# powerblade_1v0.net
KiCad netlist of a schematic drawn in EAGLE
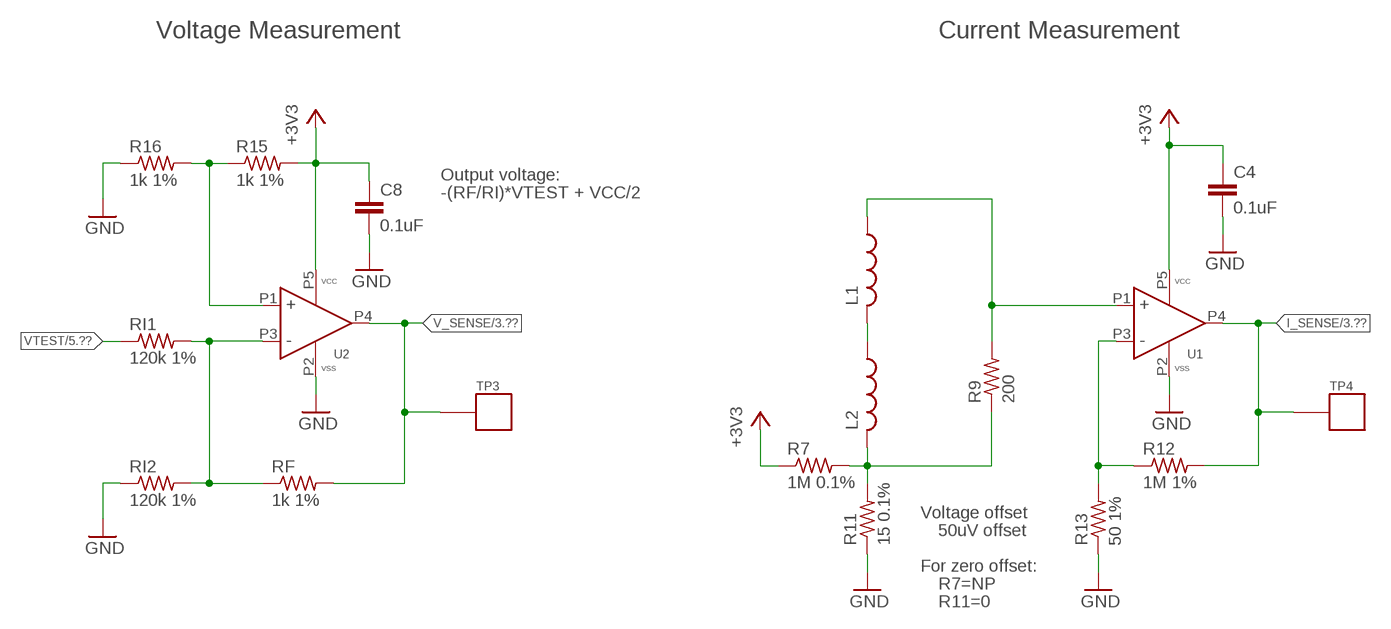
[diagram p0: schematic, sheet 1]
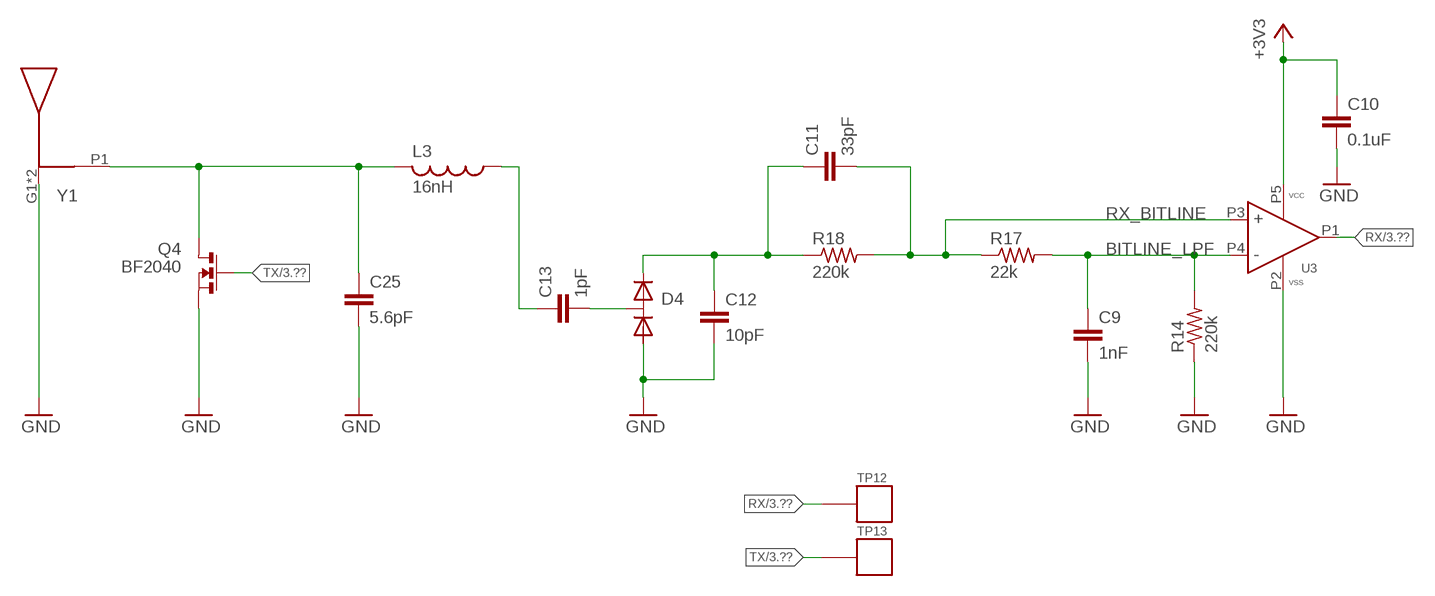
[diagram p1: schematic, sheet 2]
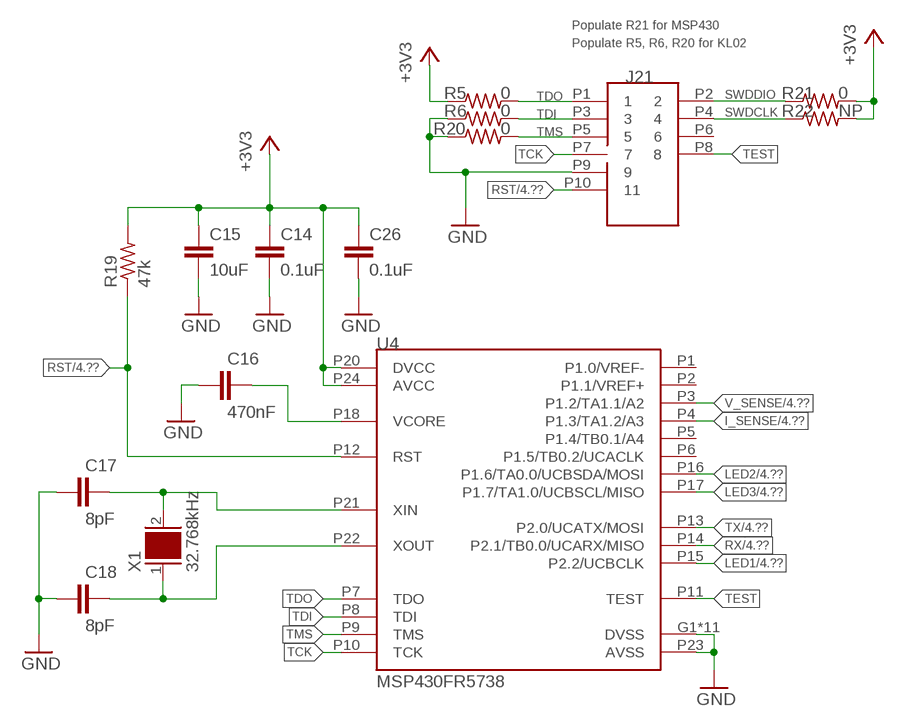
[diagram p2: schematic, sheet 3]
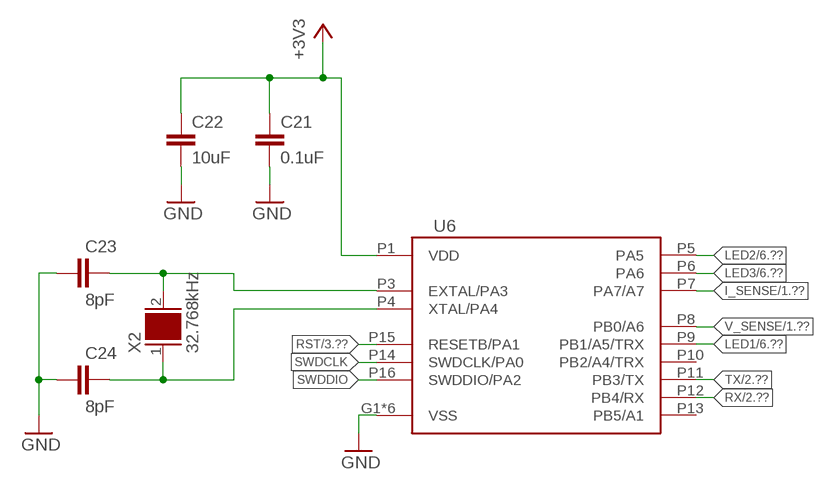
[diagram p3: schematic, sheet 4]
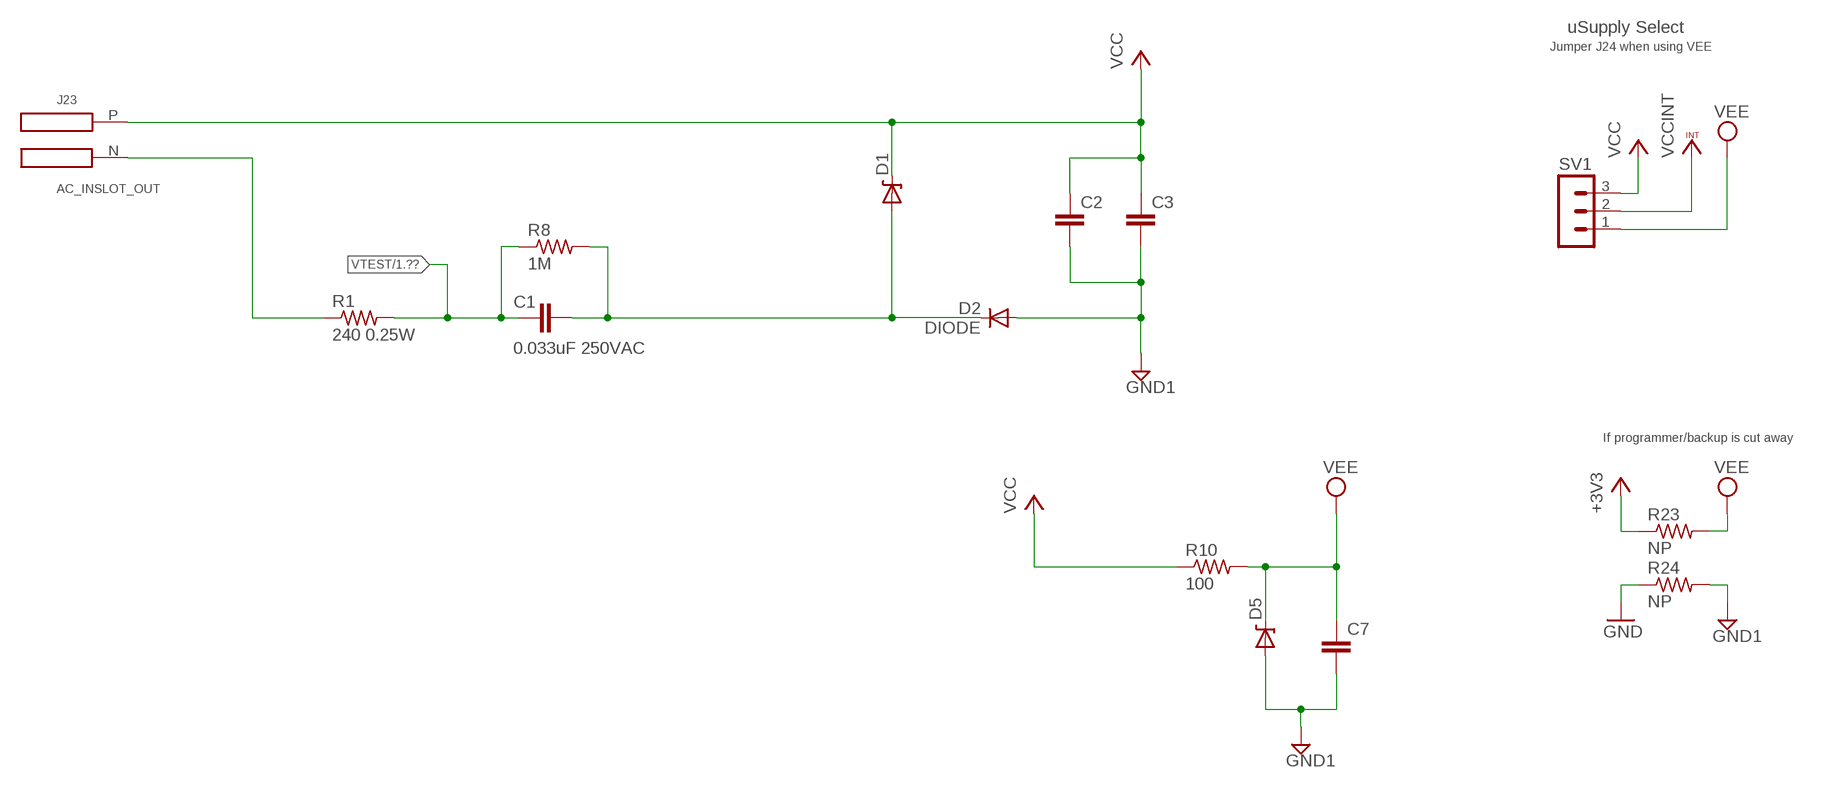
[diagram p4: schematic, sheet 5]
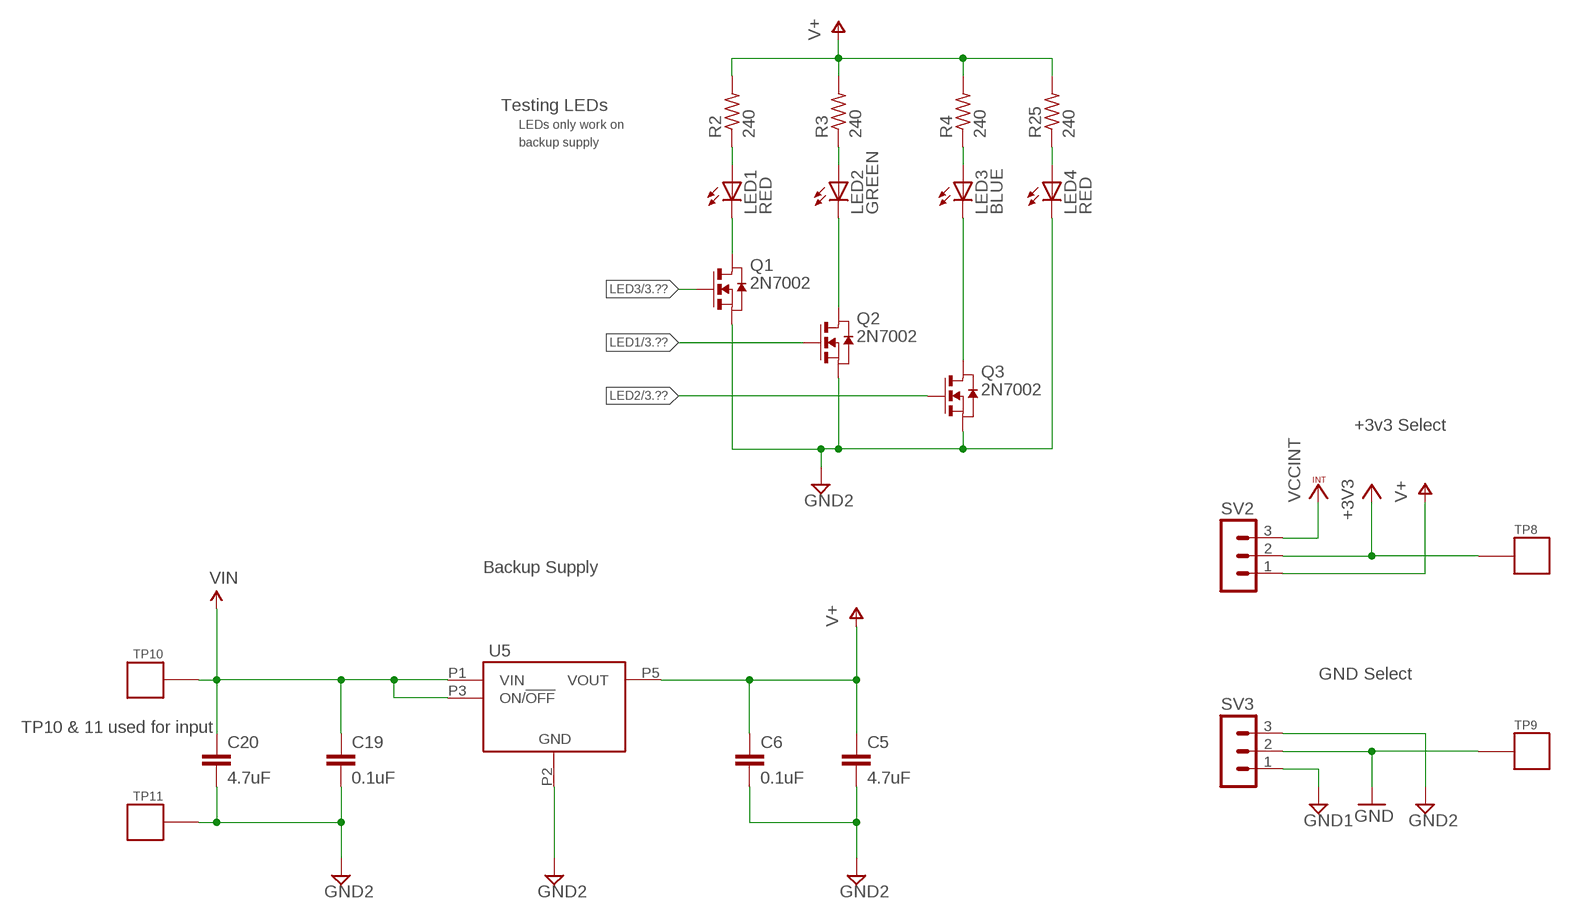
[diagram p5: schematic, sheet 6]

(export (version "E")
  (design (tool "Eeschema 10.0.6"))
  (components
    (comp (ref "C1")
      (value "0.033uF 250VAC")
      (footprint "eagle-import:C2220K")
      (libsource (lib "eagle-import") (part "C-EUC2220K"))
    )
    (comp (ref "C2")
      (value "C-EUC0805")
      (footprint "eagle-import:C0805")
      (libsource (lib "eagle-import") (part "C-EUC0805"))
    )
    (comp (ref "C3")
      (value "C-EUC0603")
      (footprint "eagle-import:C0603")
      (libsource (lib "eagle-import") (part "C-EUC0603"))
    )
    (comp (ref "C7")
      (value "C-EUC0603")
      (footprint "eagle-import:C0603")
      (libsource (lib "eagle-import") (part "C-EUC0603"))
    )
    (comp (ref "D1")
      (value "ZENERBZT52")
      (footprint "eagle-import:BZT52")
      (libsource (lib "eagle-import") (part "ZENERBZT52"))
    )
    (comp (ref "D2")
      (value "DIODE")
      (footprint "eagle-import:BAS521")
      (libsource (lib "eagle-import") (part "DIODE"))
    )
    (comp (ref "D5")
      (value "ZENERBZT52")
      (footprint "eagle-import:BZT52")
      (libsource (lib "eagle-import") (part "ZENERBZT52"))
    )
    (comp (ref "J23")
      (value "AC_INSLOT_OUT")
      (footprint "eagle-import:AC_SLOT_OUT")
      (libsource (lib "eagle-import") (part "AC_INSLOT_OUT"))
    )
    (comp (ref "R1")
      (value "240 0.25W")
      (footprint "eagle-import:R0603")
      (libsource (lib "eagle-import") (part "R-US_R0603"))
    )
    (comp (ref "R8")
      (value "1M")
      (footprint "eagle-import:R0603")
      (libsource (lib "eagle-import") (part "R-US_R0603"))
    )
    (comp (ref "R10")
      (value "100")
      (footprint "eagle-import:R0603")
      (libsource (lib "eagle-import") (part "R-US_R0603"))
    )
    (comp (ref "R23")
      (value "NP")
      (footprint "eagle-import:R0603")
      (libsource (lib "eagle-import") (part "R-US_R0603"))
    )
    (comp (ref "R24")
      (value "NP")
      (footprint "eagle-import:R0603")
      (libsource (lib "eagle-import") (part "R-US_R0603"))
    )
    (comp (ref "SV1")
      (value "MA03-1STR")
      (footprint "eagle-import:MA03-1")
      (libsource (lib "eagle-import") (part "MA03-1STR"))
    )
    (comp (ref "C5")
      (value "4.7uF")
      (footprint "eagle-import:C0603")
      (libsource (lib "eagle-import") (part "C-EUC0603"))
    )
    (comp (ref "C6")
      (value "0.1uF")
      (footprint "eagle-import:C0603")
      (libsource (lib "eagle-import") (part "C-EUC0603"))
    )
    (comp (ref "C19")
      (value "0.1uF")
      (footprint "eagle-import:C0603")
      (libsource (lib "eagle-import") (part "C-EUC0603"))
    )
    (comp (ref "C20")
      (value "4.7uF")
      (footprint "eagle-import:C0603")
      (libsource (lib "eagle-import") (part "C-EUC0603"))
    )
    (comp (ref "LED1")
      (value "RED")
      (footprint "eagle-import:LED-0603")
      (libsource (lib "eagle-import") (part "LED0603"))
    )
    (comp (ref "LED2")
      (value "GREEN")
      (footprint "eagle-import:LED-0603")
      (libsource (lib "eagle-import") (part "LED0603"))
    )
    (comp (ref "LED3")
      (value "BLUE")
      (footprint "eagle-import:LED-0603")
      (libsource (lib "eagle-import") (part "LED0603"))
    )
    (comp (ref "LED4")
      (value "RED")
      (footprint "eagle-import:LED-0603")
      (libsource (lib "eagle-import") (part "LED0603"))
    )
    (comp (ref "Q1")
      (value "2N7002")
      (footprint "eagle-import:SC-70-3")
      (libsource (lib "eagle-import") (part "2N7002"))
    )
    (comp (ref "Q2")
      (value "2N7002")
      (footprint "eagle-import:SC-70-3")
      (libsource (lib "eagle-import") (part "2N7002"))
    )
    (comp (ref "Q3")
      (value "2N7002")
      (footprint "eagle-import:SC-70-3")
      (libsource (lib "eagle-import") (part "2N7002"))
    )
    (comp (ref "R2")
      (value "240")
      (footprint "eagle-import:R0603")
      (libsource (lib "eagle-import") (part "R-US_R0603"))
    )
    (comp (ref "R3")
      (value "240")
      (footprint "eagle-import:R0603")
      (libsource (lib "eagle-import") (part "R-US_R0603"))
    )
    (comp (ref "R4")
      (value "240")
      (footprint "eagle-import:R0603")
      (libsource (lib "eagle-import") (part "R-US_R0603"))
    )
    (comp (ref "R25")
      (value "240")
      (footprint "eagle-import:R0603")
      (libsource (lib "eagle-import") (part "R-US_R0603"))
    )
    (comp (ref "SV2")
      (value "MA03-1STR")
      (footprint "eagle-import:MA03-1")
      (libsource (lib "eagle-import") (part "MA03-1STR"))
    )
    (comp (ref "SV3")
      (value "MA03-1STR")
      (footprint "eagle-import:MA03-1")
      (libsource (lib "eagle-import") (part "MA03-1STR"))
    )
    (comp (ref "TP8")
      (value "TP_STD")
      (footprint "eagle-import:TP")
      (libsource (lib "eagle-import") (part "TP_STD"))
    )
    (comp (ref "TP9")
      (value "TP_STD")
      (footprint "eagle-import:TP")
      (libsource (lib "eagle-import") (part "TP_STD"))
    )
    (comp (ref "TP10")
      (value "TP_STD")
      (footprint "eagle-import:TP")
      (libsource (lib "eagle-import") (part "TP_STD"))
    )
    (comp (ref "TP11")
      (value "TP_STD")
      (footprint "eagle-import:TP")
      (libsource (lib "eagle-import") (part "TP_STD"))
    )
    (comp (ref "U5")
      (value "LP2980")
      (footprint "eagle-import:SOT-23-5")
      (libsource (lib "eagle-import") (part "LP2980"))
    )
    (comp (ref "C14")
      (value "0.1uF")
      (footprint "eagle-import:C0603")
      (libsource (lib "eagle-import") (part "C-EUC0603"))
    )
    (comp (ref "C15")
      (value "10uF")
      (footprint "eagle-import:C0603")
      (libsource (lib "eagle-import") (part "C-EUC0603"))
    )
    (comp (ref "C16")
      (value "470nF")
      (footprint "eagle-import:C0603")
      (libsource (lib "eagle-import") (part "C-EUC0603"))
    )
    (comp (ref "C17")
      (value "8pF")
      (footprint "eagle-import:C0603")
      (libsource (lib "eagle-import") (part "C-EUC0603"))
    )
    (comp (ref "C18")
      (value "8pF")
      (footprint "eagle-import:C0603")
      (libsource (lib "eagle-import") (part "C-EUC0603"))
    )
    (comp (ref "C26")
      (value "0.1uF")
      (footprint "eagle-import:C0603")
      (libsource (lib "eagle-import") (part "C-EUC0603"))
    )
    (comp (ref "J21")
      (value "JTAG_14PIN_IDC-NL")
      (footprint "eagle-import:TC2050-IDC-NL-430")
      (fields (field (name "TAG-CONNECT") "TC2050-IDC-NL-430"))
      (libsource (lib "eagle-import") (part "JTAG_14PIN_IDC-NL"))
    )
    (comp (ref "R5")
      (value "0")
      (footprint "eagle-import:R0603")
      (libsource (lib "eagle-import") (part "R-US_R0603"))
    )
    (comp (ref "R6")
      (value "0")
      (footprint "eagle-import:R0603")
      (libsource (lib "eagle-import") (part "R-US_R0603"))
    )
    (comp (ref "R19")
      (value "47k")
      (footprint "eagle-import:R0603")
      (libsource (lib "eagle-import") (part "R-US_R0603"))
    )
    (comp (ref "R20")
      (value "0")
      (footprint "eagle-import:R0603")
      (libsource (lib "eagle-import") (part "R-US_R0603"))
    )
    (comp (ref "R21")
      (value "0")
      (footprint "eagle-import:R0603")
      (libsource (lib "eagle-import") (part "R-US_R0603"))
    )
    (comp (ref "R22")
      (value "NP")
      (footprint "eagle-import:R0603")
      (libsource (lib "eagle-import") (part "R-US_R0603"))
    )
    (comp (ref "U4")
      (value "MSP430FR5738")
      (footprint "eagle-import:VQFN-24")
      (libsource (lib "eagle-import") (part "MSP430FR5738"))
    )
    (comp (ref "X1")
      (value "32.768kHz")
      (footprint "eagle-import:0805")
      (libsource (lib "eagle-import") (part "CRYSTAL_0805"))
    )
    (comp (ref "C9")
      (value "1nF")
      (footprint "eagle-import:C0603")
      (libsource (lib "eagle-import") (part "C-EUC0603"))
    )
    (comp (ref "C10")
      (value "0.1uF")
      (footprint "eagle-import:C0603")
      (libsource (lib "eagle-import") (part "C-EUC0603"))
    )
    (comp (ref "C11")
      (value "33pF")
      (footprint "eagle-import:C0603")
      (libsource (lib "eagle-import") (part "C-EUC0603"))
    )
    (comp (ref "C12")
      (value "10pF")
      (footprint "eagle-import:C0603")
      (libsource (lib "eagle-import") (part "C-EUC0603"))
    )
    (comp (ref "C13")
      (value "1pF")
      (footprint "eagle-import:C0603")
      (libsource (lib "eagle-import") (part "C-EUC0603"))
    )
    (comp (ref "C25")
      (value "5.6pF")
      (footprint "eagle-import:C0603")
      (libsource (lib "eagle-import") (part "C-EUC0603"))
    )
    (comp (ref "D4")
      (value "HSMS-285C")
      (footprint "eagle-import:SOT-323")
      (libsource (lib "eagle-import") (part "HSMS-285C"))
    )
    (comp (ref "L3")
      (value "16nH")
      (footprint "eagle-import:L0603")
      (libsource (lib "eagle-import") (part "L-USL0603"))
    )
    (comp (ref "Q4")
      (value "BF2040")
      (footprint "eagle-import:SOT-143")
      (libsource (lib "eagle-import") (part "BF2040"))
    )
    (comp (ref "R14")
      (value "220k")
      (footprint "eagle-import:R0603")
      (libsource (lib "eagle-import") (part "R-US_R0603"))
    )
    (comp (ref "R17")
      (value "22k")
      (footprint "eagle-import:R0603")
      (libsource (lib "eagle-import") (part "R-US_R0603"))
    )
    (comp (ref "R18")
      (value "220k")
      (footprint "eagle-import:R0603")
      (libsource (lib "eagle-import") (part "R-US_R0603"))
    )
    (comp (ref "TP12")
      (value "TP_STD")
      (footprint "eagle-import:TP")
      (libsource (lib "eagle-import") (part "TP_STD"))
    )
    (comp (ref "TP13")
      (value "TP_STD")
      (footprint "eagle-import:TP")
      (libsource (lib "eagle-import") (part "TP_STD"))
    )
    (comp (ref "U3")
      (value "NCS2200S")
      (footprint "eagle-import:SC70-5")
      (libsource (lib "eagle-import") (part "NCS2200S"))
    )
    (comp (ref "Y1")
      (value "ANT-USP")
      (footprint "eagle-import:ANT-USP")
      (fields (field (name "DIGIKEY") "ANT-916-USP-ND"))
      (libsource (lib "eagle-import") (part "ANT-USP"))
    )
    (comp (ref "C21")
      (value "0.1uF")
      (footprint "eagle-import:C0603")
      (libsource (lib "eagle-import") (part "C-EUC0603"))
    )
    (comp (ref "C22")
      (value "10uF")
      (footprint "eagle-import:C0603")
      (libsource (lib "eagle-import") (part "C-EUC0603"))
    )
    (comp (ref "C23")
      (value "8pF")
      (footprint "eagle-import:C0603")
      (libsource (lib "eagle-import") (part "C-EUC0603"))
    )
    (comp (ref "C24")
      (value "8pF")
      (footprint "eagle-import:C0603")
      (libsource (lib "eagle-import") (part "C-EUC0603"))
    )
    (comp (ref "U6")
      (value "KL02")
      (footprint "eagle-import:WQFN-16")
      (libsource (lib "eagle-import") (part "KL02"))
    )
    (comp (ref "X2")
      (value "32.768kHz")
      (footprint "eagle-import:0805")
      (libsource (lib "eagle-import") (part "CRYSTAL_0805"))
    )
    (comp (ref "C4")
      (value "0.1uF")
      (footprint "eagle-import:C0402")
      (libsource (lib "eagle-import") (part "C-EUC0402"))
    )
    (comp (ref "C8")
      (value "0.1uF")
      (footprint "eagle-import:C0402")
      (libsource (lib "eagle-import") (part "C-EUC0402"))
    )
    (comp (ref "L1")
      (value "L-USL0805")
      (footprint "eagle-import:L0805")
      (libsource (lib "eagle-import") (part "L-USL0805"))
    )
    (comp (ref "L2")
      (value "L-USL0805")
      (footprint "eagle-import:L0805")
      (libsource (lib "eagle-import") (part "L-USL0805"))
    )
    (comp (ref "R7")
      (value "1M 0.1%")
      (footprint "eagle-import:R0603")
      (libsource (lib "eagle-import") (part "R-US_R0603"))
    )
    (comp (ref "R9")
      (value "200")
      (footprint "eagle-import:R0603")
      (libsource (lib "eagle-import") (part "R-US_R0603"))
    )
    (comp (ref "R11")
      (value "15 0.1%")
      (footprint "eagle-import:R0603")
      (libsource (lib "eagle-import") (part "R-US_R0603"))
    )
    (comp (ref "R12")
      (value "1M 1%")
      (footprint "eagle-import:R0603")
      (libsource (lib "eagle-import") (part "R-US_R0603"))
    )
    (comp (ref "R13")
      (value "50 1%")
      (footprint "eagle-import:R0603")
      (libsource (lib "eagle-import") (part "R-US_R0603"))
    )
    (comp (ref "R15")
      (value "1k 1%")
      (footprint "eagle-import:R0603")
      (libsource (lib "eagle-import") (part "R-US_R0603"))
    )
    (comp (ref "R16")
      (value "1k 1%")
      (footprint "eagle-import:R0603")
      (libsource (lib "eagle-import") (part "R-US_R0603"))
    )
    (comp (ref "RF")
      (value "1k 1%")
      (footprint "eagle-import:R0603")
      (libsource (lib "eagle-import") (part "R-US_R0603"))
    )
    (comp (ref "RI1")
      (value "120k 1%")
      (footprint "eagle-import:R0603")
      (libsource (lib "eagle-import") (part "R-US_R0603"))
    )
    (comp (ref "RI2")
      (value "120k 1%")
      (footprint "eagle-import:R0603")
      (libsource (lib "eagle-import") (part "R-US_R0603"))
    )
    (comp (ref "TP3")
      (value "TP_STD")
      (footprint "eagle-import:TP")
      (libsource (lib "eagle-import") (part "TP_STD"))
    )
    (comp (ref "TP4")
      (value "TP_STD")
      (footprint "eagle-import:TP")
      (libsource (lib "eagle-import") (part "TP_STD"))
    )
    (comp (ref "U1")
      (value "MAX9910")
      (footprint "eagle-import:SC70-5")
      (libsource (lib "eagle-import") (part "MAX9910"))
    )
    (comp (ref "U2")
      (value "MAX9910")
      (footprint "eagle-import:SC70-5")
      (libsource (lib "eagle-import") (part "MAX9910"))
    )
  )
  (nets
    (net (code "1") (name "+3V3") (class "Default")
      (node (ref "C10") (pin "1") (pinfunction "1_1") (pintype "passive"))
      (node (ref "C14") (pin "1") (pinfunction "1_1") (pintype "passive"))
      (node (ref "C15") (pin "1") (pinfunction "1_1") (pintype "passive"))
      (node (ref "C21") (pin "1") (pinfunction "1_1") (pintype "passive"))
      (node (ref "C22") (pin "1") (pinfunction "1_1") (pintype "passive"))
      (node (ref "C26") (pin "1") (pinfunction "1_1") (pintype "passive"))
      (node (ref "C4") (pin "1") (pinfunction "1_1") (pintype "passive"))
      (node (ref "C8") (pin "1") (pinfunction "1_1") (pintype "passive"))
      (node (ref "R15") (pin "2") (pinfunction "2_2") (pintype "passive"))
      (node (ref "R19") (pin "2") (pinfunction "2_2") (pintype "passive"))
      (node (ref "R21") (pin "2") (pinfunction "2_2") (pintype "passive"))
      (node (ref "R22") (pin "2") (pinfunction "2_2") (pintype "passive"))
      (node (ref "R23") (pin "1") (pinfunction "1_1") (pintype "passive"))
      (node (ref "R5") (pin "1") (pinfunction "1_1") (pintype "passive"))
      (node (ref "R7") (pin "1") (pinfunction "1_1") (pintype "passive"))
      (node (ref "SV2") (pin "2") (pinfunction "2_2") (pintype "passive"))
      (node (ref "TP8") (pin "P$1") (pinfunction "P$1_P$1") (pintype "bidirectional"))
      (node (ref "U1") (pin "P5") (pinfunction "VCC_P5") (pintype "bidirectional"))
      (node (ref "U2") (pin "P5") (pinfunction "VCC_P5") (pintype "bidirectional"))
      (node (ref "U3") (pin "P5") (pinfunction "VCC_P5") (pintype "bidirectional"))
      (node (ref "U4") (pin "P20") (pinfunction "DVCC_P20") (pintype "bidirectional"))
      (node (ref "U4") (pin "P24") (pinfunction "AVCC_P24") (pintype "bidirectional"))
      (node (ref "U6") (pin "P1") (pinfunction "VDD_P1") (pintype "bidirectional"))
    )
    (net (code "2") (name "BITLINE_LPF") (class "Default")
      (node (ref "C9") (pin "1") (pinfunction "1_1") (pintype "passive"))
      (node (ref "R14") (pin "2") (pinfunction "2_2") (pintype "passive"))
      (node (ref "R17") (pin "2") (pinfunction "2_2") (pintype "passive"))
      (node (ref "U3") (pin "P4") (pinfunction "IN-_P4") (pintype "bidirectional"))
    )
    (net (code "3") (name "GND") (class "Default")
      (node (ref "C10") (pin "2") (pinfunction "2_2") (pintype "passive"))
      (node (ref "C12") (pin "2") (pinfunction "2_2") (pintype "passive"))
      (node (ref "C14") (pin "2") (pinfunction "2_2") (pintype "passive"))
      (node (ref "C15") (pin "2") (pinfunction "2_2") (pintype "passive"))
      (node (ref "C16") (pin "1") (pinfunction "1_1") (pintype "passive"))
      (node (ref "C17") (pin "1") (pinfunction "1_1") (pintype "passive"))
      (node (ref "C18") (pin "1") (pinfunction "1_1") (pintype "passive"))
      (node (ref "C21") (pin "2") (pinfunction "2_2") (pintype "passive"))
      (node (ref "C22") (pin "2") (pinfunction "2_2") (pintype "passive"))
      (node (ref "C23") (pin "1") (pinfunction "1_1") (pintype "passive"))
      (node (ref "C24") (pin "1") (pinfunction "1_1") (pintype "passive"))
      (node (ref "C25") (pin "2") (pinfunction "2_2") (pintype "passive"))
      (node (ref "C26") (pin "2") (pinfunction "2_2") (pintype "passive"))
      (node (ref "C4") (pin "2") (pinfunction "2_2") (pintype "passive"))
      (node (ref "C8") (pin "2") (pinfunction "2_2") (pintype "passive"))
      (node (ref "C9") (pin "2") (pinfunction "2_2") (pintype "passive"))
      (node (ref "D4") (pin "P1") (pinfunction "P1_P1") (pintype "passive"))
      (node (ref "J21") (pin "P9") (pinfunction "9_P9") (pintype "bidirectional"))
      (node (ref "Q4") (pin "P1") (pinfunction "S_P1") (pintype "passive"))
      (node (ref "R11") (pin "1") (pinfunction "1_1") (pintype "passive"))
      (node (ref "R13") (pin "1") (pinfunction "1_1") (pintype "passive"))
      (node (ref "R14") (pin "1") (pinfunction "1_1") (pintype "passive"))
      (node (ref "R16") (pin "1") (pinfunction "1_1") (pintype "passive"))
      (node (ref "R20") (pin "1") (pinfunction "1_1") (pintype "passive"))
      (node (ref "R24") (pin "1") (pinfunction "1_1") (pintype "passive"))
      (node (ref "R6") (pin "1") (pinfunction "1_1") (pintype "passive"))
      (node (ref "RI2") (pin "1") (pinfunction "1_1") (pintype "passive"))
      (node (ref "SV3") (pin "2") (pinfunction "2_2") (pintype "passive"))
      (node (ref "TP9") (pin "P$1") (pinfunction "P$1_P$1") (pintype "bidirectional"))
      (node (ref "U1") (pin "P2") (pinfunction "VSS_P2") (pintype "bidirectional"))
      (node (ref "U2") (pin "P2") (pinfunction "VSS_P2") (pintype "bidirectional"))
      (node (ref "U3") (pin "P2") (pinfunction "VSS_P2") (pintype "bidirectional"))
      (node (ref "U4") (pin "G1") (pinfunction "DVSS_G1") (pintype "bidirectional"))
      (node (ref "U4") (pin "G2") (pinfunction "DVSS_G2") (pintype "bidirectional"))
      (node (ref "U4") (pin "G3") (pinfunction "DVSS_G3") (pintype "bidirectional"))
      (node (ref "U4") (pin "G4") (pinfunction "DVSS_G4") (pintype "bidirectional"))
      (node (ref "U4") (pin "G5") (pinfunction "DVSS_G5") (pintype "bidirectional"))
      (node (ref "U4") (pin "G6") (pinfunction "DVSS_G6") (pintype "bidirectional"))
      (node (ref "U4") (pin "G7") (pinfunction "DVSS_G7") (pintype "bidirectional"))
      (node (ref "U4") (pin "G8") (pinfunction "DVSS_G8") (pintype "bidirectional"))
      (node (ref "U4") (pin "G9") (pinfunction "DVSS_G9") (pintype "bidirectional"))
      (node (ref "U4") (pin "P19") (pinfunction "DVSS_P19") (pintype "bidirectional"))
      (node (ref "U4") (pin "P23") (pinfunction "AVSS_P23") (pintype "bidirectional"))
      (node (ref "U4") (pin "PAD") (pinfunction "DVSS_PAD") (pintype "bidirectional"))
      (node (ref "U6") (pin "G1") (pinfunction "VSS_G1") (pintype "bidirectional"))
      (node (ref "U6") (pin "G3") (pinfunction "VSS_G3") (pintype "bidirectional"))
      (node (ref "U6") (pin "G7") (pinfunction "VSS_G7") (pintype "bidirectional"))
      (node (ref "U6") (pin "G9") (pinfunction "VSS_G9") (pintype "bidirectional"))
      (node (ref "U6") (pin "P2") (pinfunction "VSS_P2") (pintype "bidirectional"))
      (node (ref "U6") (pin "PAD") (pinfunction "VSS_PAD") (pintype "bidirectional"))
      (node (ref "Y1") (pin "G1") (pinfunction "G_G1") (pintype "bidirectional"))
      (node (ref "Y1") (pin "G2") (pinfunction "G_G2") (pintype "bidirectional"))
    )
    (net (code "4") (name "GND1") (class "Default")
      (node (ref "C2") (pin "2") (pinfunction "2_2") (pintype "passive"))
      (node (ref "C3") (pin "2") (pinfunction "2_2") (pintype "passive"))
      (node (ref "C7") (pin "2") (pinfunction "2_2") (pintype "passive"))
      (node (ref "D2") (pin "A") (pinfunction "A_A") (pintype "passive"))
      (node (ref "D5") (pin "A") (pinfunction "A_A") (pintype "passive"))
      (node (ref "R24") (pin "2") (pinfunction "2_2") (pintype "passive"))
      (node (ref "SV3") (pin "1") (pinfunction "1_1") (pintype "passive"))
    )
    (net (code "5") (name "GND2") (class "Default")
      (node (ref "C19") (pin "2") (pinfunction "2_2") (pintype "passive"))
      (node (ref "C20") (pin "2") (pinfunction "2_2") (pintype "passive"))
      (node (ref "C5") (pin "2") (pinfunction "2_2") (pintype "passive"))
      (node (ref "C6") (pin "2") (pinfunction "2_2") (pintype "passive"))
      (node (ref "LED4") (pin "C") (pinfunction "C_C") (pintype "passive"))
      (node (ref "Q1") (pin "P2") (pinfunction "S_P2") (pintype "passive"))
      (node (ref "Q2") (pin "P2") (pinfunction "S_P2") (pintype "passive"))
      (node (ref "Q3") (pin "P2") (pinfunction "S_P2") (pintype "passive"))
      (node (ref "SV3") (pin "3") (pinfunction "3_3") (pintype "passive"))
      (node (ref "TP11") (pin "P$1") (pinfunction "P$1_P$1") (pintype "bidirectional"))
      (node (ref "U5") (pin "P2") (pinfunction "GND_P2") (pintype "bidirectional"))
    )
    (net (code "6") (name "I_SENSE") (class "Default")
      (node (ref "R12") (pin "2") (pinfunction "2_2") (pintype "passive"))
      (node (ref "TP4") (pin "P$1") (pinfunction "P$1_P$1") (pintype "bidirectional"))
      (node (ref "U1") (pin "P4") (pinfunction "OUT_P4") (pintype "bidirectional"))
      (node (ref "U4") (pin "P4") (pinfunction "P1.3/TA1.2/A3_P4") (pintype "bidirectional"))
      (node (ref "U6") (pin "P7") (pinfunction "PA7/A7_P7") (pintype "bidirectional"))
    )
    (net (code "7") (name "LED1") (class "Default")
      (node (ref "Q2") (pin "P1") (pinfunction "G_P1") (pintype "passive"))
      (node (ref "U4") (pin "P15") (pinfunction "P2.2/UCBCLK_P15") (pintype "bidirectional"))
      (node (ref "U6") (pin "P9") (pinfunction "PB1/A5/TRX_P9") (pintype "bidirectional"))
    )
    (net (code "8") (name "LED2") (class "Default")
      (node (ref "Q3") (pin "P1") (pinfunction "G_P1") (pintype "passive"))
      (node (ref "U4") (pin "P16") (pinfunction "P1.6/TA0.0/UCBSDA/MOSI_P16") (pintype "bidirectional"))
      (node (ref "U6") (pin "P5") (pinfunction "PA5_P5") (pintype "bidirectional"))
    )
    (net (code "9") (name "LED3") (class "Default")
      (node (ref "Q1") (pin "P1") (pinfunction "G_P1") (pintype "passive"))
      (node (ref "U4") (pin "P17") (pinfunction "P1.7/TA1.0/UCBSCL/MISO_P17") (pintype "bidirectional"))
      (node (ref "U6") (pin "P6") (pinfunction "PA6_P6") (pintype "bidirectional"))
    )
    (net (code "10") (name "Net-(C1-Pad1)") (class "Default")
      (node (ref "C1") (pin "1") (pinfunction "1_1") (pintype "passive"))
      (node (ref "D1") (pin "A") (pinfunction "A_A") (pintype "passive"))
      (node (ref "D2") (pin "C") (pinfunction "C_C") (pintype "passive"))
      (node (ref "R8") (pin "2") (pinfunction "2_2") (pintype "passive"))
    )
    (net (code "11") (name "Net-(C11-Pad1)") (class "Default")
      (node (ref "C11") (pin "1") (pinfunction "1_1") (pintype "passive"))
      (node (ref "C12") (pin "1") (pinfunction "1_1") (pintype "passive"))
      (node (ref "D4") (pin "P2") (pinfunction "P2_P2") (pintype "passive"))
      (node (ref "R18") (pin "1") (pinfunction "1_1") (pintype "passive"))
    )
    (net (code "12") (name "Net-(C13-Pad1)") (class "Default")
      (node (ref "C13") (pin "1") (pinfunction "1_1") (pintype "passive"))
      (node (ref "L3") (pin "1") (pinfunction "1_1") (pintype "passive"))
    )
    (net (code "13") (name "Net-(C13-Pad2)") (class "Default")
      (node (ref "C13") (pin "2") (pinfunction "2_2") (pintype "passive"))
      (node (ref "D4") (pin "P3") (pinfunction "P3_P3") (pintype "passive"))
    )
    (net (code "14") (name "Net-(J23-PadN)") (class "Default")
      (node (ref "J23") (pin "N") (pinfunction "N_N") (pintype "bidirectional"))
      (node (ref "R1") (pin "1") (pinfunction "1_1") (pintype "passive"))
    )
    (net (code "15") (name "Net-(L1-Pad2)") (class "Default")
      (node (ref "L1") (pin "2") (pinfunction "2_2") (pintype "passive"))
      (node (ref "L2") (pin "1") (pinfunction "1_1") (pintype "passive"))
    )
    (net (code "16") (name "Net-(L2-Pad2)") (class "Default")
      (node (ref "L2") (pin "2") (pinfunction "2_2") (pintype "passive"))
      (node (ref "R11") (pin "2") (pinfunction "2_2") (pintype "passive"))
      (node (ref "R7") (pin "2") (pinfunction "2_2") (pintype "passive"))
      (node (ref "R9") (pin "1") (pinfunction "1_1") (pintype "passive"))
    )
    (net (code "17") (name "Net-(LED1-PadA)") (class "Default")
      (node (ref "LED1") (pin "A") (pinfunction "A_A") (pintype "passive"))
      (node (ref "R2") (pin "1") (pinfunction "1_1") (pintype "passive"))
    )
    (net (code "18") (name "Net-(LED2-PadA)") (class "Default")
      (node (ref "LED2") (pin "A") (pinfunction "A_A") (pintype "passive"))
      (node (ref "R3") (pin "1") (pinfunction "1_1") (pintype "passive"))
    )
    (net (code "19") (name "Net-(LED3-PadA)") (class "Default")
      (node (ref "LED3") (pin "A") (pinfunction "A_A") (pintype "passive"))
      (node (ref "R4") (pin "1") (pinfunction "1_1") (pintype "passive"))
    )
    (net (code "20") (name "Net-(LED4-PadA)") (class "Default")
      (node (ref "LED4") (pin "A") (pinfunction "A_A") (pintype "passive"))
      (node (ref "R25") (pin "1") (pinfunction "1_1") (pintype "passive"))
    )
    (net (code "21") (name "Net-(Q1-D)") (class "Default")
      (node (ref "LED1") (pin "C") (pinfunction "C_C") (pintype "passive"))
      (node (ref "Q1") (pin "P3") (pinfunction "D_P3") (pintype "passive"))
    )
    (net (code "22") (name "Net-(Q2-D)") (class "Default")
      (node (ref "LED2") (pin "C") (pinfunction "C_C") (pintype "passive"))
      (node (ref "Q2") (pin "P3") (pinfunction "D_P3") (pintype "passive"))
    )
    (net (code "23") (name "Net-(Q3-D)") (class "Default")
      (node (ref "LED3") (pin "C") (pinfunction "C_C") (pintype "passive"))
      (node (ref "Q3") (pin "P3") (pinfunction "D_P3") (pintype "passive"))
    )
    (net (code "24") (name "Net-(Q4-D)") (class "Default")
      (node (ref "C25") (pin "1") (pinfunction "1_1") (pintype "passive"))
      (node (ref "L3") (pin "2") (pinfunction "2_2") (pintype "passive"))
      (node (ref "Q4") (pin "P2") (pinfunction "D_P2") (pintype "passive"))
      (node (ref "Y1") (pin "P1") (pinfunction "P1_P1") (pintype "bidirectional"))
    )
    (net (code "25") (name "Net-(U1-IN+)") (class "Default")
      (node (ref "L1") (pin "1") (pinfunction "1_1") (pintype "passive"))
      (node (ref "R9") (pin "2") (pinfunction "2_2") (pintype "passive"))
      (node (ref "U1") (pin "P1") (pinfunction "IN+_P1") (pintype "bidirectional"))
    )
    (net (code "26") (name "Net-(U1-IN-)") (class "Default")
      (node (ref "R12") (pin "1") (pinfunction "1_1") (pintype "passive"))
      (node (ref "R13") (pin "2") (pinfunction "2_2") (pintype "passive"))
      (node (ref "U1") (pin "P3") (pinfunction "IN-_P3") (pintype "bidirectional"))
    )
    (net (code "27") (name "Net-(U2-IN+)") (class "Default")
      (node (ref "R15") (pin "1") (pinfunction "1_1") (pintype "passive"))
      (node (ref "R16") (pin "2") (pinfunction "2_2") (pintype "passive"))
      (node (ref "U2") (pin "P1") (pinfunction "IN+_P1") (pintype "bidirectional"))
    )
    (net (code "28") (name "Net-(U2-IN-)") (class "Default")
      (node (ref "RF") (pin "1") (pinfunction "1_1") (pintype "passive"))
      (node (ref "RI1") (pin "2") (pinfunction "2_2") (pintype "passive"))
      (node (ref "RI2") (pin "2") (pinfunction "2_2") (pintype "passive"))
      (node (ref "U2") (pin "P3") (pinfunction "IN-_P3") (pintype "bidirectional"))
    )
    (net (code "29") (name "Net-(U4-VCORE)") (class "Default")
      (node (ref "C16") (pin "2") (pinfunction "2_2") (pintype "passive"))
      (node (ref "U4") (pin "P18") (pinfunction "VCORE_P18") (pintype "bidirectional"))
    )
    (net (code "30") (name "Net-(U4-XIN)") (class "Default")
      (node (ref "C17") (pin "2") (pinfunction "2_2") (pintype "passive"))
      (node (ref "U4") (pin "P21") (pinfunction "XIN_P21") (pintype "bidirectional"))
      (node (ref "X1") (pin "2") (pinfunction "P2_2") (pintype "bidirectional"))
    )
    (net (code "31") (name "Net-(U4-XOUT)") (class "Default")
      (node (ref "C18") (pin "2") (pinfunction "2_2") (pintype "passive"))
      (node (ref "U4") (pin "P22") (pinfunction "XOUT_P22") (pintype "bidirectional"))
      (node (ref "X1") (pin "1") (pinfunction "P1_1") (pintype "bidirectional"))
    )
    (net (code "32") (name "Net-(U6-EXTAL{slash}PA3)") (class "Default")
      (node (ref "C23") (pin "2") (pinfunction "2_2") (pintype "passive"))
      (node (ref "U6") (pin "P3") (pinfunction "EXTAL/PA3_P3") (pintype "bidirectional"))
      (node (ref "X2") (pin "2") (pinfunction "P2_2") (pintype "bidirectional"))
    )
    (net (code "33") (name "Net-(U6-XTAL{slash}PA4)") (class "Default")
      (node (ref "C24") (pin "2") (pinfunction "2_2") (pintype "passive"))
      (node (ref "U6") (pin "P4") (pinfunction "XTAL/PA4_P4") (pintype "bidirectional"))
      (node (ref "X2") (pin "1") (pinfunction "P1_1") (pintype "bidirectional"))
    )
    (net (code "34") (name "RST") (class "Default")
      (node (ref "J21") (pin "P10") (pinfunction "11_P10") (pintype "bidirectional"))
      (node (ref "R19") (pin "1") (pinfunction "1_1") (pintype "passive"))
      (node (ref "U4") (pin "P12") (pinfunction "RST_P12") (pintype "bidirectional"))
      (node (ref "U6") (pin "P15") (pinfunction "RESETB/PA1_P15") (pintype "bidirectional"))
    )
    (net (code "35") (name "RX") (class "Default")
      (node (ref "TP12") (pin "P$1") (pinfunction "P$1_P$1") (pintype "bidirectional"))
      (node (ref "U3") (pin "P1") (pinfunction "OUT_P1") (pintype "bidirectional"))
      (node (ref "U4") (pin "P14") (pinfunction "P2.1/TB0.0/UCARX/MISO_P14") (pintype "bidirectional"))
      (node (ref "U6") (pin "P12") (pinfunction "PB4/RX_P12") (pintype "bidirectional"))
    )
    (net (code "36") (name "RX_BITLINE") (class "Default")
      (node (ref "C11") (pin "2") (pinfunction "2_2") (pintype "passive"))
      (node (ref "R17") (pin "1") (pinfunction "1_1") (pintype "passive"))
      (node (ref "R18") (pin "2") (pinfunction "2_2") (pintype "passive"))
      (node (ref "U3") (pin "P3") (pinfunction "IN+_P3") (pintype "bidirectional"))
    )
    (net (code "37") (name "SWDCLK") (class "Default")
      (node (ref "J21") (pin "P4") (pinfunction "4_P4") (pintype "bidirectional"))
      (node (ref "R22") (pin "1") (pinfunction "1_1") (pintype "passive"))
      (node (ref "U6") (pin "P14") (pinfunction "SWDCLK/PA0_P14") (pintype "bidirectional"))
    )
    (net (code "38") (name "SWDDIO") (class "Default")
      (node (ref "J21") (pin "P2") (pinfunction "2_P2") (pintype "bidirectional"))
      (node (ref "R21") (pin "1") (pinfunction "1_1") (pintype "passive"))
      (node (ref "U6") (pin "P16") (pinfunction "SWDDIO/PA2_P16") (pintype "bidirectional"))
    )
    (net (code "39") (name "TCK") (class "Default")
      (node (ref "J21") (pin "P7") (pinfunction "7_P7") (pintype "bidirectional"))
      (node (ref "U4") (pin "P10") (pinfunction "TCK_P10") (pintype "bidirectional"))
    )
    (net (code "40") (name "TDI") (class "Default")
      (node (ref "J21") (pin "P3") (pinfunction "3_P3") (pintype "bidirectional"))
      (node (ref "R6") (pin "2") (pinfunction "2_2") (pintype "passive"))
      (node (ref "U4") (pin "P8") (pinfunction "TDI_P8") (pintype "bidirectional"))
    )
    (net (code "41") (name "TDO") (class "Default")
      (node (ref "J21") (pin "P1") (pinfunction "1_P1") (pintype "bidirectional"))
      (node (ref "R5") (pin "2") (pinfunction "2_2") (pintype "passive"))
      (node (ref "U4") (pin "P7") (pinfunction "TDO_P7") (pintype "bidirectional"))
    )
    (net (code "42") (name "TEST") (class "Default")
      (node (ref "J21") (pin "P8") (pinfunction "8_P8") (pintype "bidirectional"))
      (node (ref "U4") (pin "P11") (pinfunction "TEST_P11") (pintype "bidirectional"))
    )
    (net (code "43") (name "TMS") (class "Default")
      (node (ref "J21") (pin "P5") (pinfunction "5_P5") (pintype "bidirectional"))
      (node (ref "R20") (pin "2") (pinfunction "2_2") (pintype "passive"))
      (node (ref "U4") (pin "P9") (pinfunction "TMS_P9") (pintype "bidirectional"))
    )
    (net (code "44") (name "TX") (class "Default")
      (node (ref "Q4") (pin "P3") (pinfunction "G_P3") (pintype "passive"))
      (node (ref "Q4") (pin "P4") (pinfunction "G_P4") (pintype "passive"))
      (node (ref "TP13") (pin "P$1") (pinfunction "P$1_P$1") (pintype "bidirectional"))
      (node (ref "U4") (pin "P13") (pinfunction "P2.0/UCATX/MOSI_P13") (pintype "bidirectional"))
      (node (ref "U6") (pin "P11") (pinfunction "PB3/TX_P11") (pintype "bidirectional"))
    )
    (net (code "45") (name "V+") (class "Default")
      (node (ref "C5") (pin "1") (pinfunction "1_1") (pintype "passive"))
      (node (ref "C6") (pin "1") (pinfunction "1_1") (pintype "passive"))
      (node (ref "R2") (pin "2") (pinfunction "2_2") (pintype "passive"))
      (node (ref "R25") (pin "2") (pinfunction "2_2") (pintype "passive"))
      (node (ref "R3") (pin "2") (pinfunction "2_2") (pintype "passive"))
      (node (ref "R4") (pin "2") (pinfunction "2_2") (pintype "passive"))
      (node (ref "SV2") (pin "1") (pinfunction "1_1") (pintype "passive"))
      (node (ref "U5") (pin "P5") (pinfunction "VOUT_P5") (pintype "bidirectional"))
    )
    (net (code "46") (name "VCC") (class "Default")
      (node (ref "C2") (pin "1") (pinfunction "1_1") (pintype "passive"))
      (node (ref "C3") (pin "1") (pinfunction "1_1") (pintype "passive"))
      (node (ref "D1") (pin "C") (pinfunction "C_C") (pintype "passive"))
      (node (ref "J23") (pin "P") (pinfunction "P_P") (pintype "bidirectional"))
      (node (ref "R10") (pin "1") (pinfunction "1_1") (pintype "passive"))
      (node (ref "SV1") (pin "3") (pinfunction "3_3") (pintype "passive"))
    )
    (net (code "47") (name "VCCINT") (class "Default")
      (node (ref "SV1") (pin "2") (pinfunction "2_2") (pintype "passive"))
      (node (ref "SV2") (pin "3") (pinfunction "3_3") (pintype "passive"))
    )
    (net (code "48") (name "VEE") (class "Default")
      (node (ref "C7") (pin "1") (pinfunction "1_1") (pintype "passive"))
      (node (ref "D5") (pin "C") (pinfunction "C_C") (pintype "passive"))
      (node (ref "R10") (pin "2") (pinfunction "2_2") (pintype "passive"))
      (node (ref "R23") (pin "2") (pinfunction "2_2") (pintype "passive"))
      (node (ref "SV1") (pin "1") (pinfunction "1_1") (pintype "passive"))
    )
    (net (code "49") (name "VIN") (class "Default")
      (node (ref "C19") (pin "1") (pinfunction "1_1") (pintype "passive"))
      (node (ref "C20") (pin "1") (pinfunction "1_1") (pintype "passive"))
      (node (ref "TP10") (pin "P$1") (pinfunction "P$1_P$1") (pintype "bidirectional"))
      (node (ref "U5") (pin "P1") (pinfunction "VIN_P1") (pintype "bidirectional"))
      (node (ref "U5") (pin "P3") (pinfunction "ON/~{OFF}_P3") (pintype "bidirectional"))
    )
    (net (code "50") (name "VTEST") (class "Default")
      (node (ref "C1") (pin "2") (pinfunction "2_2") (pintype "passive"))
      (node (ref "R1") (pin "2") (pinfunction "2_2") (pintype "passive"))
      (node (ref "R8") (pin "1") (pinfunction "1_1") (pintype "passive"))
      (node (ref "RI1") (pin "1") (pinfunction "1_1") (pintype "passive"))
    )
    (net (code "51") (name "V_SENSE") (class "Default")
      (node (ref "RF") (pin "2") (pinfunction "2_2") (pintype "passive"))
      (node (ref "TP3") (pin "P$1") (pinfunction "P$1_P$1") (pintype "bidirectional"))
      (node (ref "U2") (pin "P4") (pinfunction "OUT_P4") (pintype "bidirectional"))
      (node (ref "U4") (pin "P3") (pinfunction "P1.2/TA1.1/A2_P3") (pintype "bidirectional"))
      (node (ref "U6") (pin "P8") (pinfunction "PB0/A6_P8") (pintype "bidirectional"))
    )
    (net (code "52") (name "unconnected-(J21-6-PadP6)") (class "Default")
      (node (ref "J21") (pin "P6") (pinfunction "6_P6") (pintype "bidirectional"))
    )
    (net (code "53") (name "unconnected-(U4-P1.0{slash}VREF--PadP1)") (class "Default")
      (node (ref "U4") (pin "P1") (pinfunction "P1.0/VREF-_P1") (pintype "bidirectional"))
    )
    (net (code "54") (name "unconnected-(U4-P1.1{slash}VREF+-PadP2)") (class "Default")
      (node (ref "U4") (pin "P2") (pinfunction "P1.1/VREF+_P2") (pintype "bidirectional"))
    )
    (net (code "55") (name "unconnected-(U4-P1.4{slash}TB0.1{slash}A4-PadP5)") (class "Default")
      (node (ref "U4") (pin "P5") (pinfunction "P1.4/TB0.1/A4_P5") (pintype "bidirectional"))
    )
    (net (code "56") (name "unconnected-(U4-P1.5{slash}TB0.2{slash}UCACLK-PadP6)") (class "Default")
      (node (ref "U4") (pin "P6") (pinfunction "P1.5/TB0.2/UCACLK_P6") (pintype "bidirectional"))
    )
    (net (code "57") (name "unconnected-(U6-PB2{slash}A4{slash}TRX-PadP10)") (class "Default")
      (node (ref "U6") (pin "P10") (pinfunction "PB2/A4/TRX_P10") (pintype "bidirectional"))
    )
    (net (code "58") (name "unconnected-(U6-PB5{slash}A1-PadP13)") (class "Default")
      (node (ref "U6") (pin "P13") (pinfunction "PB5/A1_P13") (pintype "bidirectional"))
    )
  )
)
